# SIM_dummy.net
KiCad netlist of a schematic drawn in EAGLE
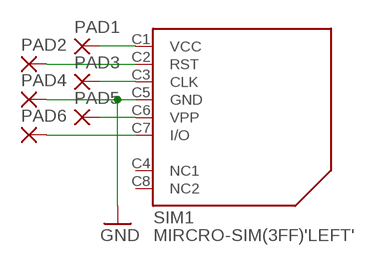
[diagram p0: schematic, sheet 1]

(export (version "E")
  (design (tool "Eeschema 10.0.6"))
  (components
    (comp (ref "PAD1")
      (value "SMD2")
      (footprint "eagle-import:SMD1,27-2,54")
      (libsource (lib "eagle-import") (part "SMD2"))
    )
    (comp (ref "PAD2")
      (value "SMD2")
      (footprint "eagle-import:SMD1,27-2,54")
      (libsource (lib "eagle-import") (part "SMD2"))
    )
    (comp (ref "PAD3")
      (value "SMD2")
      (footprint "eagle-import:SMD1,27-2,54")
      (libsource (lib "eagle-import") (part "SMD2"))
    )
    (comp (ref "PAD4")
      (value "SMD2")
      (footprint "eagle-import:SMD1,27-2,54")
      (libsource (lib "eagle-import") (part "SMD2"))
    )
    (comp (ref "PAD5")
      (value "SMD2")
      (footprint "eagle-import:SMD1,27-2,54")
      (libsource (lib "eagle-import") (part "SMD2"))
    )
    (comp (ref "PAD6")
      (value "SMD2")
      (footprint "eagle-import:SMD1,27-2,54")
      (libsource (lib "eagle-import") (part "SMD2"))
    )
    (comp (ref "SIM1")
      (value "MIRCRO-SIM(3FF)'LEFT'")
      (footprint "eagle-import:MICRO-SIM_LEFT")
      (libsource (lib "eagle-import") (part "MIRCRO-SIM(3FF)'LEFT'"))
    )
  )
  (nets
    (net (code "1") (name "GND") (class "Default")
      (node (ref "PAD4") (pin "1") (pinfunction "P_1") (pintype "passive"))
      (node (ref "SIM1") (pin "C5") (pinfunction "GND_C5") (pintype "bidirectional"))
    )
    (net (code "2") (name "Net-(PAD1-P)") (class "Default")
      (node (ref "PAD1") (pin "1") (pinfunction "P_1") (pintype "passive"))
      (node (ref "SIM1") (pin "C1") (pinfunction "VCC_C1") (pintype "bidirectional"))
    )
    (net (code "3") (name "Net-(PAD2-P)") (class "Default")
      (node (ref "PAD2") (pin "1") (pinfunction "P_1") (pintype "passive"))
      (node (ref "SIM1") (pin "C2") (pinfunction "RST_C2") (pintype "bidirectional"))
    )
    (net (code "4") (name "Net-(PAD3-P)") (class "Default")
      (node (ref "PAD3") (pin "1") (pinfunction "P_1") (pintype "passive"))
      (node (ref "SIM1") (pin "C3") (pinfunction "CLK_C3") (pintype "bidirectional"))
    )
    (net (code "5") (name "Net-(PAD5-P)") (class "Default")
      (node (ref "PAD5") (pin "1") (pinfunction "P_1") (pintype "passive"))
      (node (ref "SIM1") (pin "C6") (pinfunction "VPP_C6") (pintype "bidirectional"))
    )
    (net (code "6") (name "Net-(PAD6-P)") (class "Default")
      (node (ref "PAD6") (pin "1") (pinfunction "P_1") (pintype "passive"))
      (node (ref "SIM1") (pin "C7") (pinfunction "I/O_C7") (pintype "bidirectional"))
    )
    (net (code "7") (name "unconnected-(SIM1-NC1-PadC4)") (class "Default")
      (node (ref "SIM1") (pin "C4") (pinfunction "NC1_C4") (pintype "bidirectional"))
    )
    (net (code "8") (name "unconnected-(SIM1-NC2-PadC8)") (class "Default")
      (node (ref "SIM1") (pin "C8") (pinfunction "NC2_C8") (pintype "bidirectional"))
    )
  )
)
